# EasyEDA_Schematic.net
KiCad netlist of a schematic drawn in EasyEDA
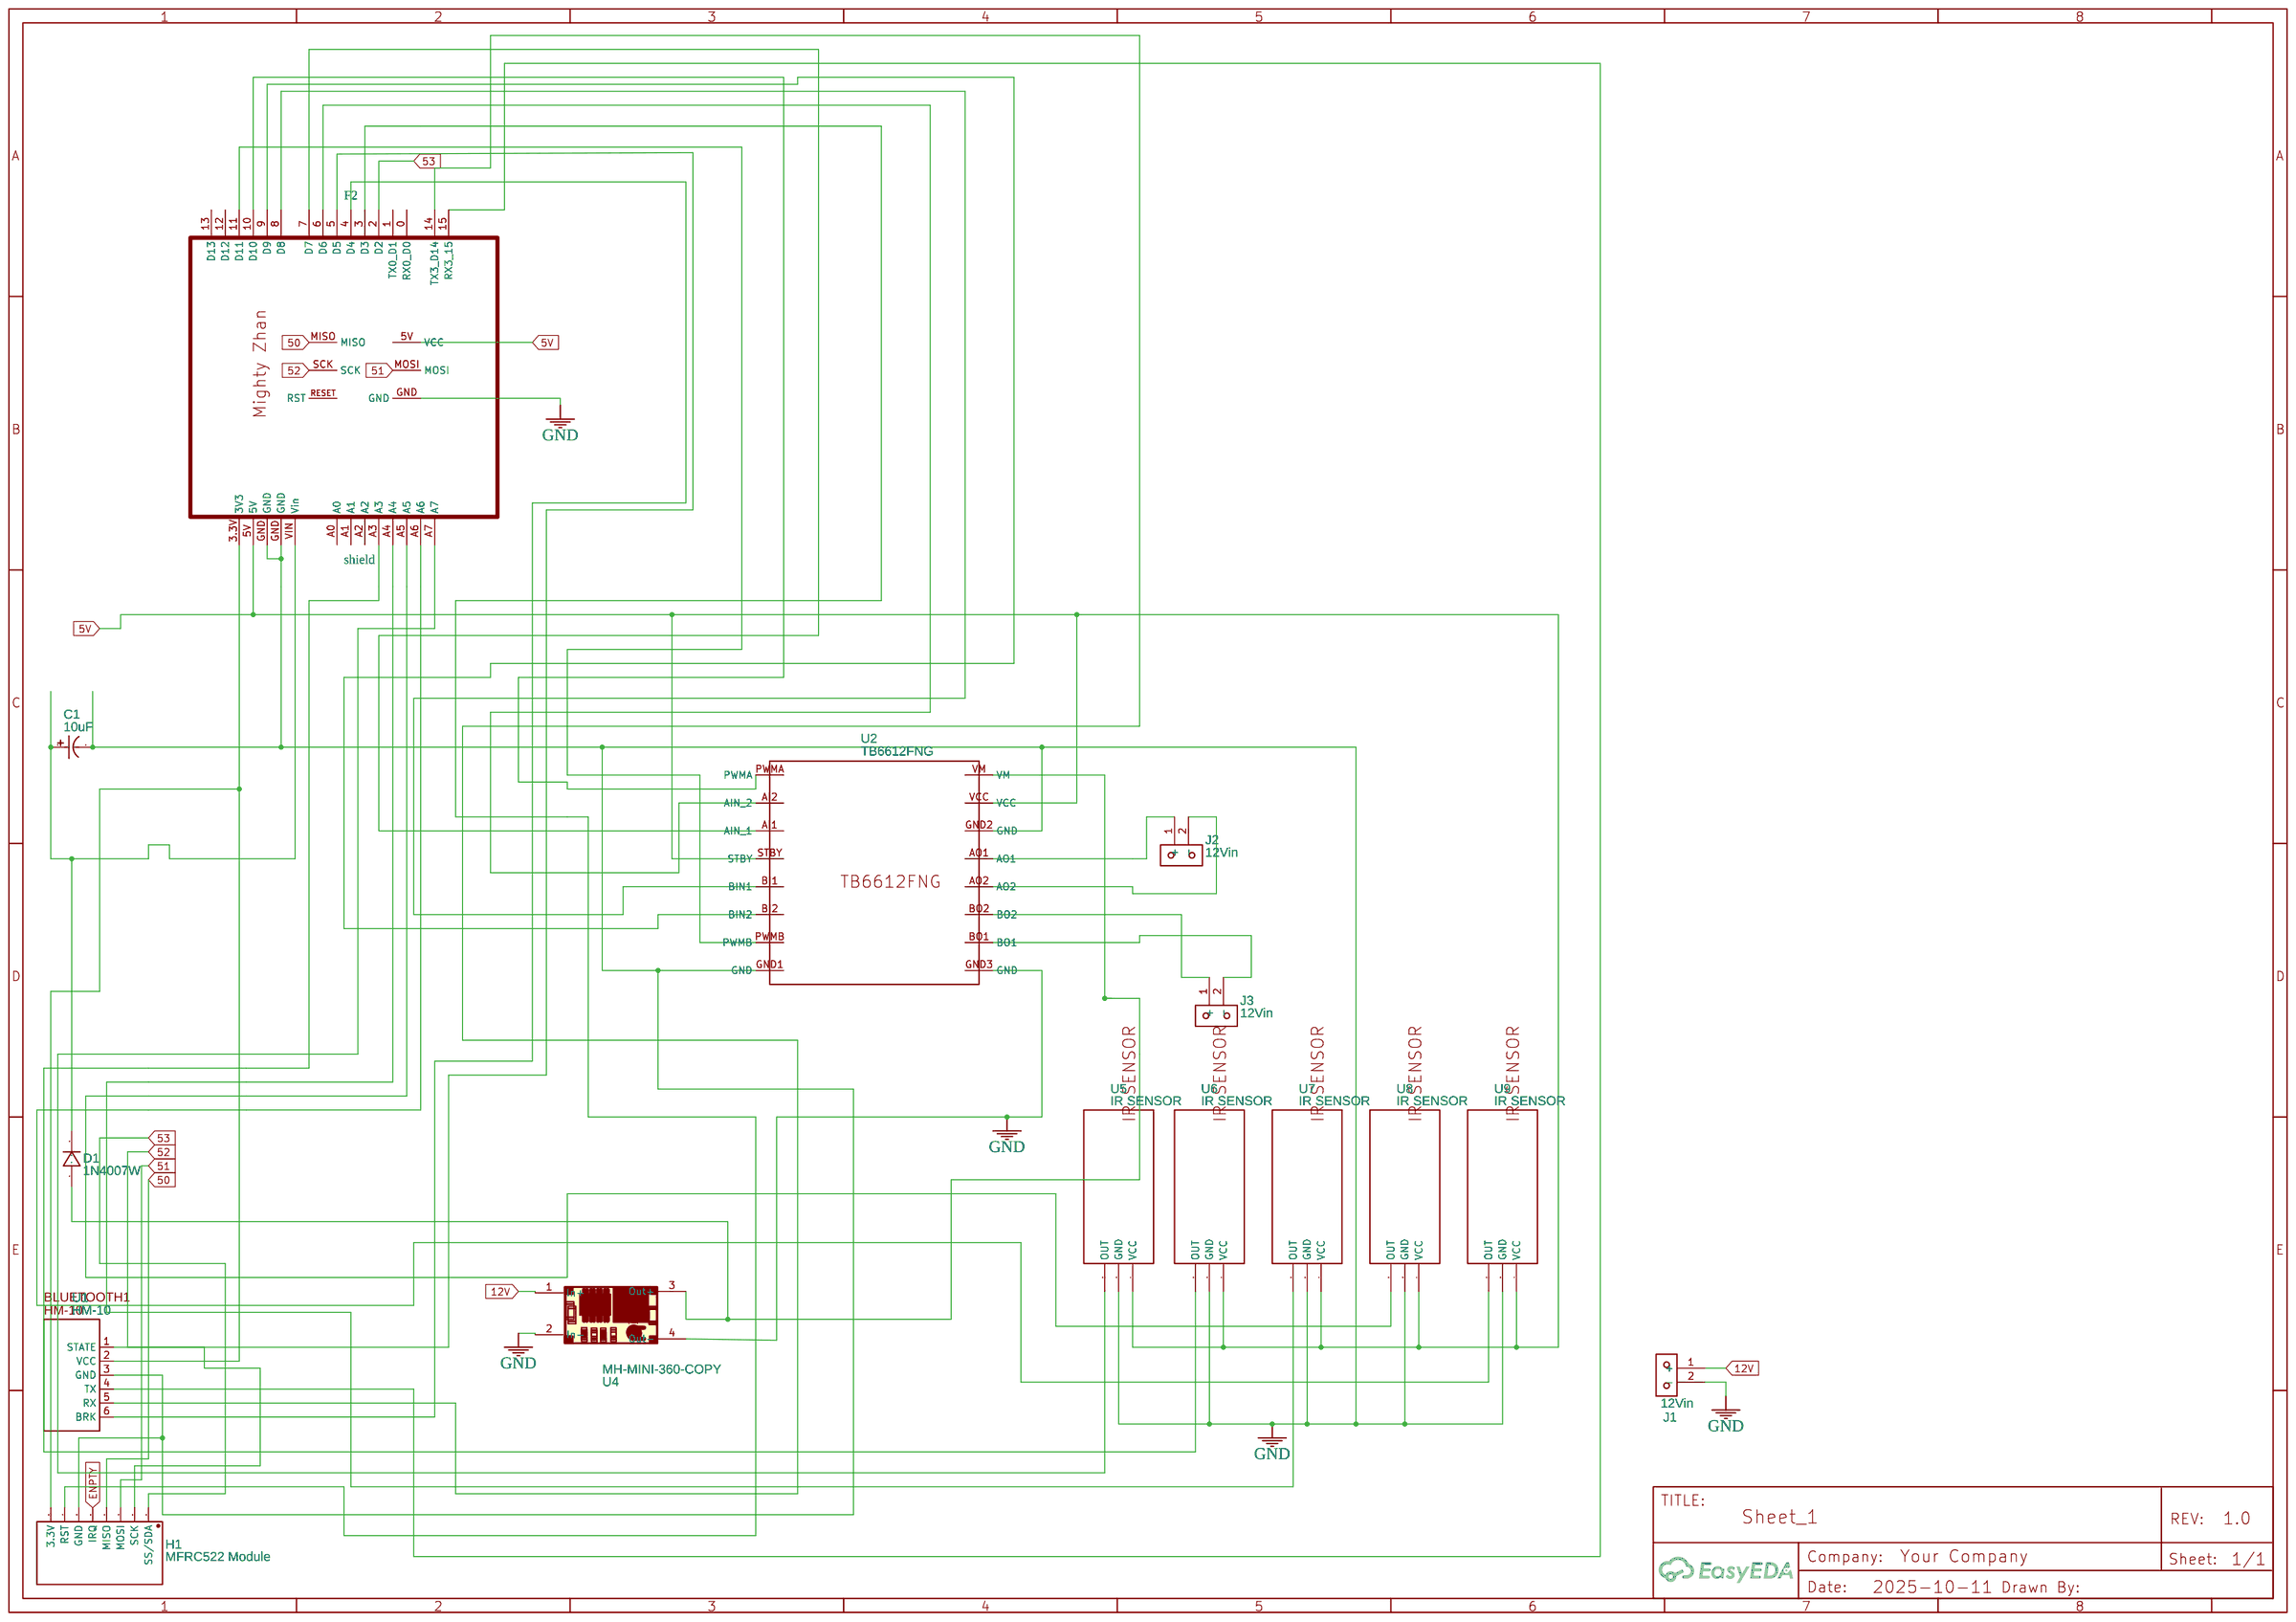
[diagram p0: schematic sheet]

(export (version "E")
  (design (tool "Eeschema 10.0.6"))
  (components
    (comp (ref "C1")
      (value "10uF")
      (fields
        (field (name "Manufacturer Part") "KS106M050C07RR0VH2FP0")
        (field (name "Manufacturer") "CX(承兴)")
      )
      (libsource (lib "") (part "electrolytic capacitor10UF50V"))
    )
    (comp (ref "D1")
      (value "1N4007W")
      (fields (field (name "Manufacturer") "BLUE ROCKET"))
      (libsource (lib "") (part "1N4007W"))
    )
    (comp (ref "F2") (value "shield") (libsource (lib "") (part "Unknown_240_-885")))
    (comp (ref "H1")
      (value "MFRC522 Module")
      (fields
        (field (name "Manufacturer Part") "210S-1*8P L=11.6MMGold-plated black")
        (field (name "Manufacturer") "Ckmtw")
      )
      (libsource (lib "") (part "MFRC522 Module"))
    )
    (comp (ref "J1")
      (value "12Vin")
      (fields
        (field (name "Manufacturer Part") "OSTTA024163")
        (field (name "Manufacturer") "On Shore Technology Inc.")
      )
      (libsource (lib "") (part "ED2580-ND_1"))
    )
    (comp (ref "J2")
      (value "12Vin")
      (fields
        (field (name "Manufacturer Part") "OSTTA024163")
        (field (name "Manufacturer") "On Shore Technology Inc.")
      )
      (libsource (lib "") (part "ED2580-ND"))
    )
    (comp (ref "J3")
      (value "12Vin")
      (fields
        (field (name "Manufacturer Part") "OSTTA024163")
        (field (name "Manufacturer") "On Shore Technology Inc.")
      )
      (libsource (lib "") (part "ED2580-ND"))
    )
    (comp (ref "U1") (value "HM-10") (libsource (lib "") (part "HM-10")))
    (comp (ref "U2") (value "TB6612FNG") (libsource (lib "") (part "TB6612FNG")))
    (comp (ref "U4") (value "MH-MINI-360-COPY") (libsource (lib "") (part "MH-MINI-360-COPY")))
    (comp (ref "U5") (value "IR SENSOR") (libsource (lib "") (part "MH-Sensor-Series Line Sensor")))
    (comp (ref "U6") (value "IR SENSOR") (libsource (lib "") (part "MH-Sensor-Series Line Sensor")))
    (comp (ref "U7") (value "IR SENSOR") (libsource (lib "") (part "MH-Sensor-Series Line Sensor")))
    (comp (ref "U8") (value "IR SENSOR") (libsource (lib "") (part "MH-Sensor-Series Line Sensor")))
    (comp (ref "U9") (value "IR SENSOR") (libsource (lib "") (part "MH-Sensor-Series Line Sensor")))
  )
  (nets
    (net (code "1") (name "5V") (class "Default")
      (node (ref "F2") (pin "5V") (pinfunction "5V_5V") (pintype "unspecified"))
      (node (ref "U2") (pin "STBY") (pinfunction "STBY_STBY") (pintype "unspecified"))
      (node (ref "U2") (pin "VCC") (pinfunction "VCC_VCC") (pintype "unspecified"))
      (node (ref "U5") (pin "4") (pinfunction "VCC_4") (pintype "unspecified"))
      (node (ref "U6") (pin "4") (pinfunction "VCC_4") (pintype "unspecified"))
      (node (ref "U7") (pin "4") (pinfunction "VCC_4") (pintype "unspecified"))
      (node (ref "U8") (pin "4") (pinfunction "VCC_4") (pintype "unspecified"))
      (node (ref "U9") (pin "4") (pinfunction "VCC_4") (pintype "unspecified"))
    )
    (net (code "2") (name "12V") (class "Default")
      (node (ref "J1") (pin "1") (pinfunction "+_1") (pintype "input"))
      (node (ref "U4") (pin "1") (pinfunction "In+_1") (pintype "unspecified"))
    )
    (net (code "3") (name "50") (class "Default")
      (node (ref "F2") (pin "MISO") (pinfunction "MISO_MISO") (pintype "unspecified"))
      (node (ref "H1") (pin "4") (pinfunction "MISO_4") (pintype "unspecified"))
    )
    (net (code "4") (name "51") (class "Default")
      (node (ref "F2") (pin "MOSI") (pinfunction "MOSI_MOSI") (pintype "unspecified"))
      (node (ref "H1") (pin "3") (pinfunction "MOSI_3") (pintype "unspecified"))
    )
    (net (code "5") (name "52") (class "Default")
      (node (ref "F2") (pin "SCK") (pinfunction "SCK_SCK") (pintype "unspecified"))
      (node (ref "H1") (pin "2") (pinfunction "SCK_2") (pintype "unspecified"))
    )
    (net (code "6") (name "53") (class "Default")
      (node (ref "F2") (pin "2") (pinfunction "D2_2") (pintype "unspecified"))
      (node (ref "H1") (pin "1") (pinfunction "SS/SDA_1") (pintype "unspecified"))
    )
    (net (code "7") (name "ENPTY") (class "Default")
      (node (ref "H1") (pin "5") (pinfunction "IRQ_5") (pintype "unspecified"))
    )
    (net (code "8") (name "GND") (class "Default")
      (node (ref "C1") (pin "2") (pinfunction "-_2") (pintype "input"))
      (node (ref "F2") (pin "GND") (pinfunction "GND_GND") (pintype "unspecified"))
      (node (ref "H1") (pin "6") (pinfunction "GND_6") (pintype "unspecified"))
      (node (ref "J1") (pin "2") (pinfunction "-_2") (pintype "input"))
      (node (ref "U1") (pin "3") (pinfunction "GND_3") (pintype "unspecified"))
      (node (ref "U2") (pin "GND1") (pinfunction "GND_GND1") (pintype "unspecified"))
      (node (ref "U2") (pin "GND2") (pinfunction "GND_GND2") (pintype "unspecified"))
      (node (ref "U2") (pin "GND3") (pinfunction "GND_GND3") (pintype "unspecified"))
      (node (ref "U4") (pin "2") (pinfunction "In-_2") (pintype "unspecified"))
      (node (ref "U4") (pin "4") (pinfunction "Out-_4") (pintype "unspecified"))
      (node (ref "U5") (pin "3") (pinfunction "GND_3") (pintype "unspecified"))
      (node (ref "U6") (pin "3") (pinfunction "GND_3") (pintype "unspecified"))
      (node (ref "U7") (pin "3") (pinfunction "GND_3") (pintype "unspecified"))
      (node (ref "U8") (pin "3") (pinfunction "GND_3") (pintype "unspecified"))
      (node (ref "U9") (pin "3") (pinfunction "GND_3") (pintype "unspecified"))
    )
    (net (code "9") (name "Net-(C1-+)") (class "Default")
      (node (ref "C1") (pin "1") (pinfunction "+_1") (pintype "input"))
      (node (ref "D1") (pin "2") (pinfunction "1_2") (pintype "unspecified"))
      (node (ref "F2") (pin "VIN") (pinfunction "Vin_VIN") (pintype "unspecified"))
    )
    (net (code "10") (name "Net-(D1-2)") (class "Default")
      (node (ref "D1") (pin "1") (pinfunction "2_1") (pintype "unspecified"))
      (node (ref "U2") (pin "VM") (pinfunction "VM_VM") (pintype "unspecified"))
      (node (ref "U4") (pin "3") (pinfunction "Out+_3") (pintype "unspecified"))
    )
    (net (code "11") (name "Net-(F2-3V3)") (class "Default")
      (node (ref "F2") (pin "3.3V") (pinfunction "3V3_3.3V") (pintype "unspecified"))
      (node (ref "H1") (pin "8") (pinfunction "3.3V_8") (pintype "unspecified"))
      (node (ref "U1") (pin "2") (pinfunction "VCC_2") (pintype "unspecified"))
    )
    (net (code "12") (name "Net-(F2-D3)") (class "Default")
      (node (ref "F2") (pin "3") (pinfunction "D3_3") (pintype "unspecified"))
      (node (ref "H1") (pin "7") (pinfunction "RST_7") (pintype "unspecified"))
    )
    (net (code "13") (name "Net-(F2-D4)") (class "Default")
      (node (ref "F2") (pin "4") (pinfunction "D4_4") (pintype "unspecified"))
      (node (ref "U1") (pin "6") (pinfunction "BRK_6") (pintype "unspecified"))
    )
    (net (code "14") (name "Net-(F2-D5)") (class "Default")
      (node (ref "F2") (pin "5") (pinfunction "D5_5") (pintype "unspecified"))
      (node (ref "U1") (pin "1") (pinfunction "STATE_1") (pintype "unspecified"))
    )
    (net (code "15") (name "Net-(F2-D6)") (class "Default")
      (node (ref "F2") (pin "6") (pinfunction "D6_6") (pintype "unspecified"))
      (node (ref "U2") (pin "AI2") (pinfunction "AIN_2_AI2") (pintype "unspecified"))
    )
    (net (code "16") (name "Net-(F2-D7)") (class "Default")
      (node (ref "F2") (pin "7") (pinfunction "D7_7") (pintype "unspecified"))
      (node (ref "U2") (pin "AI1") (pinfunction "AIN_1_AI1") (pintype "unspecified"))
    )
    (net (code "17") (name "Net-(F2-D8)") (class "Default")
      (node (ref "F2") (pin "8") (pinfunction "D8_8") (pintype "unspecified"))
      (node (ref "U2") (pin "BI1") (pinfunction "BIN1_BI1") (pintype "unspecified"))
    )
    (net (code "18") (name "Net-(F2-D9)") (class "Default")
      (node (ref "F2") (pin "9") (pinfunction "D9_9") (pintype "unspecified"))
      (node (ref "U2") (pin "BI2") (pinfunction "BIN2_BI2") (pintype "unspecified"))
    )
    (net (code "19") (name "Net-(F2-D10)") (class "Default")
      (node (ref "F2") (pin "10") (pinfunction "D10_10") (pintype "unspecified"))
      (node (ref "U2") (pin "PWMA") (pinfunction "PWMA_PWMA") (pintype "unspecified"))
    )
    (net (code "20") (name "Net-(F2-D11)") (class "Default")
      (node (ref "F2") (pin "11") (pinfunction "D11_11") (pintype "unspecified"))
      (node (ref "U2") (pin "PWMB") (pinfunction "PWMB_PWMB") (pintype "unspecified"))
    )
    (net (code "21") (name "Net-(F2-RX3_15)") (class "Default")
      (node (ref "F2") (pin "15") (pinfunction "RX3_15_15") (pintype "unspecified"))
      (node (ref "U1") (pin "4") (pinfunction "TX_4") (pintype "unspecified"))
    )
    (net (code "22") (name "Net-(F2-TX3_D14)") (class "Default")
      (node (ref "F2") (pin "14") (pinfunction "TX3_D14_14") (pintype "unspecified"))
      (node (ref "U1") (pin "5") (pinfunction "RX_5") (pintype "unspecified"))
    )
    (net (code "23") (name "Net-(J2-+)") (class "Default")
      (node (ref "J2") (pin "1") (pinfunction "+_1") (pintype "input"))
      (node (ref "U2") (pin "AO1") (pinfunction "AO1_AO1") (pintype "unspecified"))
    )
    (net (code "24") (name "Net-(J2--)") (class "Default")
      (node (ref "J2") (pin "2") (pinfunction "-_2") (pintype "input"))
      (node (ref "U2") (pin "AO2") (pinfunction "AO2_AO2") (pintype "unspecified"))
    )
    (net (code "25") (name "Net-(J3-+)") (class "Default")
      (node (ref "J3") (pin "1") (pinfunction "+_1") (pintype "input"))
      (node (ref "U2") (pin "BO2") (pinfunction "BO2_BO2") (pintype "unspecified"))
    )
    (net (code "26") (name "Net-(J3--)") (class "Default")
      (node (ref "J3") (pin "2") (pinfunction "-_2") (pintype "input"))
      (node (ref "U2") (pin "BO1") (pinfunction "BO1_BO1") (pintype "unspecified"))
    )
    (net (code "27") (name "Net-(U5-OUT)") (class "Default")
      (node (ref "F2") (pin "A7") (pinfunction "A7_A7") (pintype "unspecified"))
      (node (ref "U5") (pin "2") (pinfunction "OUT_2") (pintype "unspecified"))
    )
    (net (code "28") (name "Net-(U6-OUT)") (class "Default")
      (node (ref "F2") (pin "A3") (pinfunction "A3_A3") (pintype "unspecified"))
      (node (ref "U6") (pin "2") (pinfunction "OUT_2") (pintype "unspecified"))
    )
    (net (code "29") (name "Net-(U7-OUT)") (class "Default")
      (node (ref "F2") (pin "A4") (pinfunction "A4_A4") (pintype "unspecified"))
      (node (ref "U7") (pin "2") (pinfunction "OUT_2") (pintype "unspecified"))
    )
    (net (code "30") (name "Net-(U8-OUT)") (class "Default")
      (node (ref "F2") (pin "A5") (pinfunction "A5_A5") (pintype "unspecified"))
      (node (ref "U8") (pin "2") (pinfunction "OUT_2") (pintype "unspecified"))
    )
    (net (code "31") (name "Net-(U9-OUT)") (class "Default")
      (node (ref "F2") (pin "A6") (pinfunction "A6_A6") (pintype "unspecified"))
      (node (ref "U9") (pin "2") (pinfunction "OUT_2") (pintype "unspecified"))
    )
    (net (code "32") (name "unconnected-(F2-D12-Pad12)") (class "Default")
      (node (ref "F2") (pin "12") (pinfunction "D12_12") (pintype "unspecified"))
    )
    (net (code "33") (name "unconnected-(F2-D13-Pad13)") (class "Default")
      (node (ref "F2") (pin "13") (pinfunction "D13_13") (pintype "unspecified"))
    )
    (net (code "34") (name "unconnected-(F2-PadA0)") (class "Default")
      (node (ref "F2") (pin "A0") (pinfunction "A0_A0") (pintype "unspecified"))
    )
    (net (code "35") (name "unconnected-(F2-PadA1)") (class "Default")
      (node (ref "F2") (pin "A1") (pinfunction "A1_A1") (pintype "unspecified"))
    )
    (net (code "36") (name "unconnected-(F2-PadA2)") (class "Default")
      (node (ref "F2") (pin "A2") (pinfunction "A2_A2") (pintype "unspecified"))
    )
    (net (code "37") (name "unconnected-(F2-RST-PadRESET)") (class "Default")
      (node (ref "F2") (pin "RESET") (pinfunction "RST_RESET") (pintype "unspecified"))
    )
    (net (code "38") (name "unconnected-(F2-RX0_D0-Pad0)") (class "Default")
      (node (ref "F2") (pin "0") (pinfunction "RX0_D0_0") (pintype "unspecified"))
    )
    (net (code "39") (name "unconnected-(F2-TX0_D1-Pad1)") (class "Default")
      (node (ref "F2") (pin "1") (pinfunction "TX0_D1_1") (pintype "unspecified"))
    )
  )
)
